# design.net
KiCad netlist of a schematic drawn in Altium Designer
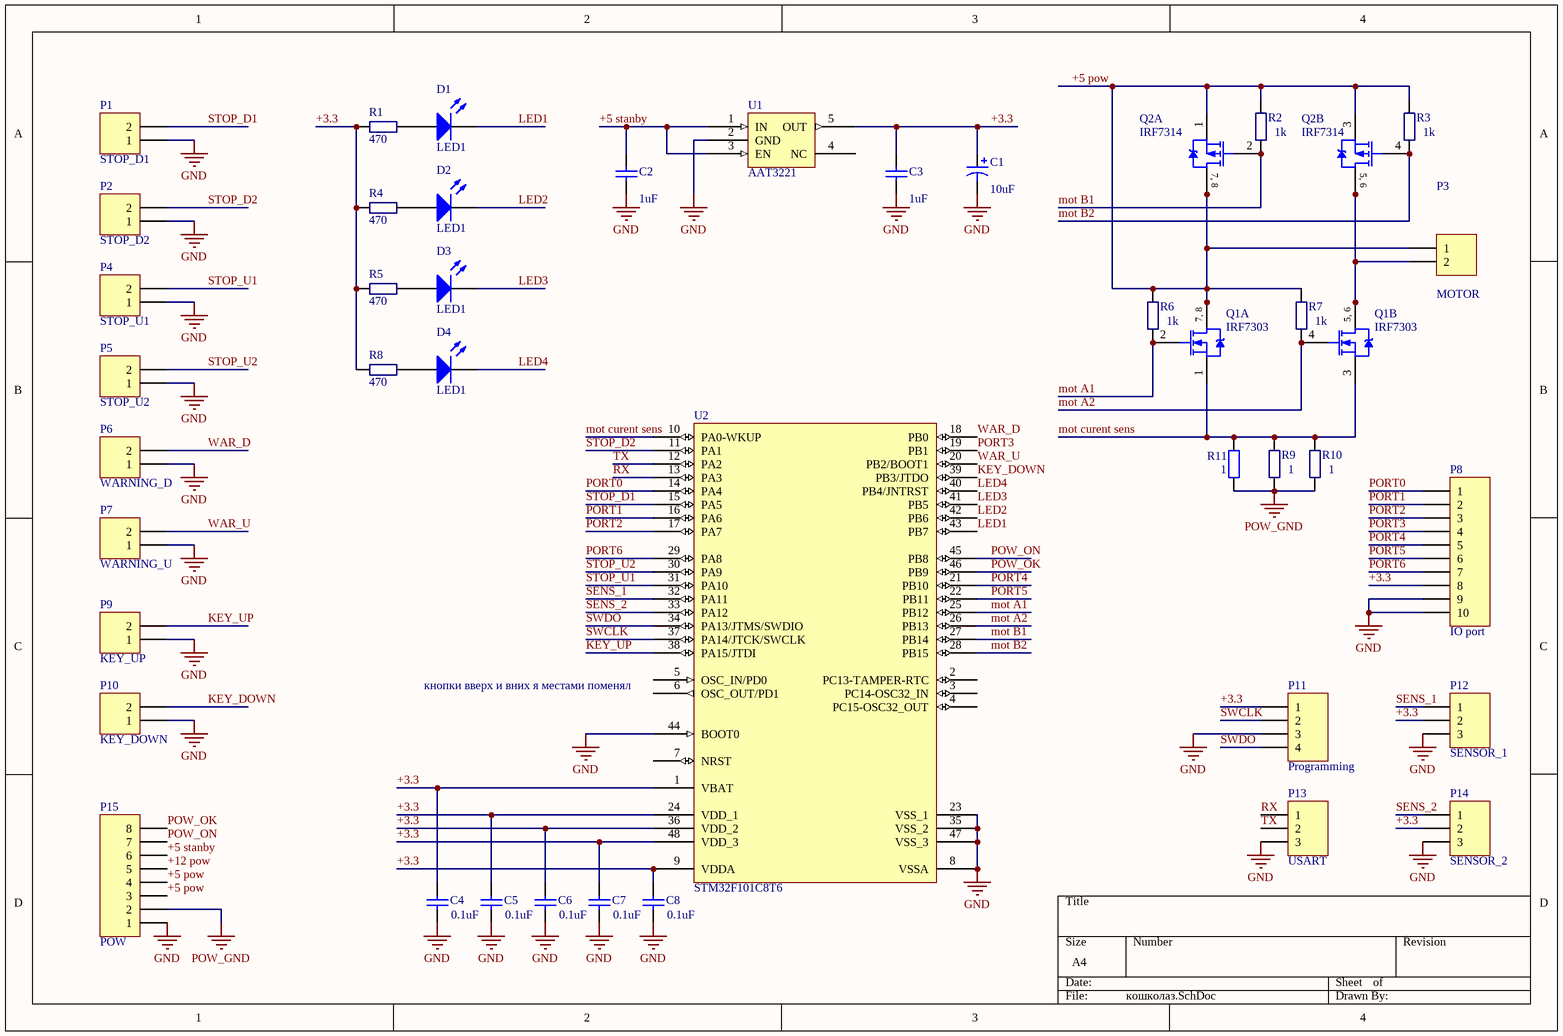
[diagram p0: кошколаз.SchDoc]

(export (version "E")
  (design (tool "Eeschema 10.0.6"))
  (components
    (comp (ref "C1")
      (value "10uF")
      (footprint "C0805")
      (description "Polarized Capacitor (Surface Mount)")
      (fields (field (name "PUBLISHER") "Altium Limited"))
      (libsource (lib "Miscellaneous Devices") (part "Cap Pol3"))
    )
    (comp (ref "C2")
      (value "1uF")
      (footprint "1608[0603]")
      (description "Capacitor (Semiconductor SIM Model)")
      (fields (field (name "PUBLISHER") "Altium Limited"))
      (libsource (lib "Miscellaneous Devices") (part "Cap Semi"))
    )
    (comp (ref "C3")
      (value "1uF")
      (footprint "1608[0603]")
      (description "Capacitor (Semiconductor SIM Model)")
      (fields (field (name "PUBLISHER") "Altium Limited"))
      (libsource (lib "Miscellaneous Devices") (part "Cap Semi"))
    )
    (comp (ref "C4")
      (value "0.1uF")
      (footprint "1608[0603]")
      (description "Capacitor (Semiconductor SIM Model)")
      (fields (field (name "PUBLISHER") "Altium Limited"))
      (libsource (lib "Miscellaneous Devices") (part "Cap Semi"))
    )
    (comp (ref "C5")
      (value "0.1uF")
      (footprint "1608[0603]")
      (description "Capacitor (Semiconductor SIM Model)")
      (fields (field (name "PUBLISHER") "Altium Limited"))
      (libsource (lib "Miscellaneous Devices") (part "Cap Semi"))
    )
    (comp (ref "C6")
      (value "0.1uF")
      (footprint "1608[0603]")
      (description "Capacitor (Semiconductor SIM Model)")
      (fields (field (name "PUBLISHER") "Altium Limited"))
      (libsource (lib "Miscellaneous Devices") (part "Cap Semi"))
    )
    (comp (ref "C7")
      (value "0.1uF")
      (footprint "1608[0603]")
      (description "Capacitor (Semiconductor SIM Model)")
      (fields (field (name "PUBLISHER") "Altium Limited"))
      (libsource (lib "Miscellaneous Devices") (part "Cap Semi"))
    )
    (comp (ref "C8")
      (value "0.1uF")
      (footprint "1608[0603]")
      (description "Capacitor (Semiconductor SIM Model)")
      (fields (field (name "PUBLISHER") "Altium Limited"))
      (libsource (lib "Miscellaneous Devices") (part "Cap Semi"))
    )
    (comp (ref "D1")
      (value "LED1")
      (footprint "LED-1")
      (description "Typical RED GaAs LED")
      (fields (field (name "PUBLISHER") "Altium Limited"))
      (libsource (lib "Miscellaneous Devices") (part "LED1"))
    )
    (comp (ref "D2")
      (value "LED1")
      (footprint "LED-1")
      (description "Typical RED GaAs LED")
      (fields (field (name "PUBLISHER") "Altium Limited"))
      (libsource (lib "Miscellaneous Devices") (part "LED1"))
    )
    (comp (ref "D3")
      (value "LED1")
      (footprint "LED-1")
      (description "Typical RED GaAs LED")
      (fields (field (name "PUBLISHER") "Altium Limited"))
      (libsource (lib "Miscellaneous Devices") (part "LED1"))
    )
    (comp (ref "D4")
      (value "LED1")
      (footprint "LED-1")
      (description "Typical RED GaAs LED")
      (fields (field (name "PUBLISHER") "Altium Limited"))
      (libsource (lib "Miscellaneous Devices") (part "LED1"))
    )
    (comp (ref "P1")
      (value "STOP_D1")
      (footprint "HDR1X2")
      (description "Header, 2-Pin")
      (fields (field (name "PUBLISHER") "Altium Limited"))
      (libsource (lib "Miscellaneous Connectors") (part "Header 2"))
    )
    (comp (ref "P2")
      (value "STOP_D2")
      (footprint "HDR1X2")
      (description "Header, 2-Pin")
      (fields (field (name "PUBLISHER") "Altium Limited"))
      (libsource (lib "Miscellaneous Connectors") (part "Header 2"))
    )
    (comp (ref "P3")
      (value "MOTOR")
      (footprint "HDR1X2")
      (description "Header, 2-Pin")
      (fields (field (name "PUBLISHER") "Altium Limited"))
      (libsource (lib "") (part "Header 2_1"))
    )
    (comp (ref "P4")
      (value "STOP_U1")
      (footprint "HDR1X2")
      (description "Header, 2-Pin")
      (fields (field (name "PUBLISHER") "Altium Limited"))
      (libsource (lib "Miscellaneous Connectors") (part "Header 2"))
    )
    (comp (ref "P5")
      (value "STOP_U2")
      (footprint "HDR1X2")
      (description "Header, 2-Pin")
      (fields (field (name "PUBLISHER") "Altium Limited"))
      (libsource (lib "Miscellaneous Connectors") (part "Header 2"))
    )
    (comp (ref "P6")
      (value "WARNING_D")
      (footprint "HDR1X2")
      (description "Header, 2-Pin")
      (fields (field (name "PUBLISHER") "Altium Limited"))
      (libsource (lib "Miscellaneous Connectors") (part "Header 2"))
    )
    (comp (ref "P7")
      (value "WARNING_U")
      (footprint "HDR1X2")
      (description "Header, 2-Pin")
      (fields (field (name "PUBLISHER") "Altium Limited"))
      (libsource (lib "Miscellaneous Connectors") (part "Header 2"))
    )
    (comp (ref "P8")
      (value "IO port")
      (footprint "HDR1X10")
      (description "Header, 10-Pin")
      (fields (field (name "PUBLISHER") "Altium Limited"))
      (libsource (lib "Miscellaneous Connectors") (part "Header 10"))
    )
    (comp (ref "P9")
      (value "KEY_UP")
      (footprint "HDR1X2")
      (description "Header, 2-Pin")
      (fields (field (name "PUBLISHER") "Altium Limited"))
      (libsource (lib "Miscellaneous Connectors") (part "Header 2"))
    )
    (comp (ref "P10")
      (value "KEY_DOWN")
      (footprint "HDR1X2")
      (description "Header, 2-Pin")
      (fields (field (name "PUBLISHER") "Altium Limited"))
      (libsource (lib "Miscellaneous Connectors") (part "Header 2"))
    )
    (comp (ref "P11")
      (value "Programming")
      (footprint "HDR1X4")
      (description "Header, 4-Pin")
      (fields (field (name "PUBLISHER") "Altium Limited"))
      (libsource (lib "Miscellaneous Connectors") (part "Header 4"))
    )
    (comp (ref "P12")
      (value "SENSOR_1")
      (footprint "HDR1X3")
      (description "Header, 3-Pin")
      (fields (field (name "PUBLISHER") "Altium Limited"))
      (libsource (lib "Miscellaneous Connectors") (part "Header 3"))
    )
    (comp (ref "P13")
      (value "USART")
      (footprint "HDR1X3")
      (description "Header, 3-Pin")
      (fields (field (name "PUBLISHER") "Altium Limited"))
      (libsource (lib "Miscellaneous Connectors") (part "Header 3"))
    )
    (comp (ref "P14")
      (value "SENSOR_2")
      (footprint "HDR1X3")
      (description "Header, 3-Pin")
      (fields (field (name "PUBLISHER") "Altium Limited"))
      (libsource (lib "Miscellaneous Connectors") (part "Header 3"))
    )
    (comp (ref "P15")
      (value "POW")
      (footprint "HDR1X8")
      (description "Header, 8-Pin")
      (fields (field (name "PUBLISHER") "Altium Limited"))
      (libsource (lib "Miscellaneous Connectors") (part "Header 8"))
    )
    (comp (ref "Q1")
      (value "IRF7303")
      (footprint "SO-8_N")
      (description "HEXFET Power MOSFET")
      (fields (field (name "PUBLISHER") "Altium Limited"))
      (libsource (lib "IR Discrete MOSFET - Power") (part "IRF7303"))
    )
    (comp (ref "Q2")
      (value "IRF7314")
      (footprint "SO-8_N")
      (description "HEXFET Power MOSFET")
      (fields (field (name "PUBLISHER") "Altium Limited"))
      (libsource (lib "IR Discrete MOSFET - Power") (part "IRF7314"))
    )
    (comp (ref "R1")
      (value "470")
      (footprint "J1-0603")
      (description "Resistor")
      (fields (field (name "PUBLISHER") "Altium Limited"))
      (libsource (lib "LockLib") (part "Res_SMD"))
    )
    (comp (ref "R2")
      (value "1k")
      (footprint "J1-0603")
      (description "Resistor")
      (fields (field (name "PUBLISHER") "Altium Limited"))
      (libsource (lib "LockLib") (part "Res_SMD"))
    )
    (comp (ref "R3")
      (value "1k")
      (footprint "J1-0603")
      (description "Resistor")
      (fields (field (name "PUBLISHER") "Altium Limited"))
      (libsource (lib "LockLib") (part "Res_SMD"))
    )
    (comp (ref "R4")
      (value "470")
      (footprint "J1-0603")
      (description "Resistor")
      (fields (field (name "PUBLISHER") "Altium Limited"))
      (libsource (lib "LockLib") (part "Res_SMD"))
    )
    (comp (ref "R5")
      (value "470")
      (footprint "J1-0603")
      (description "Resistor")
      (fields (field (name "PUBLISHER") "Altium Limited"))
      (libsource (lib "LockLib") (part "Res_SMD"))
    )
    (comp (ref "R6")
      (value "1k")
      (footprint "J1-0603")
      (description "Resistor")
      (fields (field (name "PUBLISHER") "Altium Limited"))
      (libsource (lib "LockLib") (part "Res_SMD"))
    )
    (comp (ref "R7")
      (value "1k")
      (footprint "J1-0603")
      (description "Resistor")
      (fields (field (name "PUBLISHER") "Altium Limited"))
      (libsource (lib "LockLib") (part "Res_SMD"))
    )
    (comp (ref "R8")
      (value "470")
      (footprint "J1-0603")
      (description "Resistor")
      (fields (field (name "PUBLISHER") "Altium Limited"))
      (libsource (lib "LockLib") (part "Res_SMD"))
    )
    (comp (ref "R9")
      (value "1")
      (footprint "6-0805_N")
      (description "Resistor")
      (fields (field (name "PUBLISHER") "Altium Limited"))
      (libsource (lib "LockLib") (part "Res_SMD"))
    )
    (comp (ref "R10")
      (value "1")
      (footprint "6-0805_N")
      (description "Resistor")
      (fields (field (name "PUBLISHER") "Altium Limited"))
      (libsource (lib "LockLib") (part "Res_SMD"))
    )
    (comp (ref "R11")
      (value "1")
      (footprint "AXIAL-0.4")
      (description "Resistor")
      (fields (field (name "PUBLISHER") "Altium Limited"))
      (libsource (lib "Miscellaneous Devices") (part "Res2"))
    )
    (comp (ref "U1")
      (value "AAT3221")
      (footprint "SOT23-5")
      (description "Low Dropout Linear Regulator")
      (libsource (lib "LockLib") (part "AAT3221"))
    )
    (comp (ref "U2")
      (value "STM32F101C8T6")
      (footprint "LQFP48_M")
      (description "STM32 ARM-based 32-bit MCU with 64 Kbytes Flash, 48-pin LQFP, Industrial Temperature")
      (fields (field (name "PUBLISHER") "Altium Limited"))
      (libsource (lib "ST Microcontroller 32-Bit STM32") (part "STM32F101C8T6"))
    )
  )
  (nets
    (net (code "1") (name "/+3.3") (class "Default")
      (node (ref "C1") (pin "1") (pinfunction "1_1") (pintype "passive"))
      (node (ref "C3") (pin "2") (pinfunction "2_2") (pintype "passive"))
      (node (ref "C4") (pin "2") (pinfunction "2_2") (pintype "passive"))
      (node (ref "C5") (pin "2") (pinfunction "2_2") (pintype "passive"))
      (node (ref "C6") (pin "2") (pinfunction "2_2") (pintype "passive"))
      (node (ref "C7") (pin "2") (pinfunction "2_2") (pintype "passive"))
      (node (ref "C8") (pin "2") (pinfunction "2_2") (pintype "passive"))
      (node (ref "P11") (pin "1") (pinfunction "1_1") (pintype "passive"))
      (node (ref "P12") (pin "2") (pinfunction "2_2") (pintype "passive"))
      (node (ref "P14") (pin "2") (pinfunction "2_2") (pintype "passive"))
      (node (ref "P8") (pin "8") (pinfunction "8_8") (pintype "passive"))
      (node (ref "R1") (pin "2") (pinfunction "2_2") (pintype "passive"))
      (node (ref "R4") (pin "2") (pinfunction "2_2") (pintype "passive"))
      (node (ref "R5") (pin "2") (pinfunction "2_2") (pintype "passive"))
      (node (ref "R8") (pin "2") (pinfunction "2_2") (pintype "passive"))
      (node (ref "U1") (pin "5") (pinfunction "OUT_5") (pintype "output"))
      (node (ref "U2") (pin "1") (pinfunction "VBAT_1") (pintype "power_in"))
      (node (ref "U2") (pin "24") (pinfunction "VDD_1_24") (pintype "power_in"))
      (node (ref "U2") (pin "36") (pinfunction "VDD_2_36") (pintype "power_in"))
      (node (ref "U2") (pin "48") (pinfunction "VDD_3_48") (pintype "power_in"))
      (node (ref "U2") (pin "9") (pinfunction "VDDA_9") (pintype "power_in"))
    )
    (net (code "2") (name "/+5 pow") (class "Default")
      (node (ref "P15") (pin "3") (pinfunction "3_3") (pintype "passive"))
      (node (ref "P15") (pin "4") (pinfunction "4_4") (pintype "passive"))
      (node (ref "P3") (pin "1") (pinfunction "1_1") (pintype "passive"))
      (node (ref "Q1") (pin "7") (pinfunction "D_7") (pintype "passive"))
      (node (ref "Q1") (pin "8") (pinfunction "D_8") (pintype "passive"))
      (node (ref "Q2") (pin "1") (pinfunction "S_1") (pintype "passive"))
      (node (ref "Q2") (pin "3") (pinfunction "S_3") (pintype "passive"))
      (node (ref "Q2") (pin "7") (pinfunction "D_7") (pintype "passive"))
      (node (ref "Q2") (pin "8") (pinfunction "D_8") (pintype "passive"))
      (node (ref "R2") (pin "2") (pinfunction "2_2") (pintype "passive"))
      (node (ref "R3") (pin "2") (pinfunction "2_2") (pintype "passive"))
      (node (ref "R6") (pin "2") (pinfunction "2_2") (pintype "passive"))
      (node (ref "R7") (pin "2") (pinfunction "2_2") (pintype "passive"))
    )
    (net (code "3") (name "/+5 stanby") (class "Default")
      (node (ref "C2") (pin "2") (pinfunction "2_2") (pintype "passive"))
      (node (ref "P15") (pin "6") (pinfunction "6_6") (pintype "passive"))
      (node (ref "U1") (pin "1") (pinfunction "IN_1") (pintype "input"))
      (node (ref "U1") (pin "3") (pinfunction "EN_3") (pintype "input"))
    )
    (net (code "4") (name "/+12 pow") (class "Default")
      (node (ref "P15") (pin "5") (pinfunction "5_5") (pintype "passive"))
    )
    (net (code "5") (name "/KEY_DOWN") (class "Default")
      (node (ref "P10") (pin "2") (pinfunction "2_2") (pintype "passive"))
      (node (ref "U2") (pin "39") (pinfunction "PB3/JTDO_39") (pintype "bidirectional"))
    )
    (net (code "6") (name "/KEY_UP") (class "Default")
      (node (ref "P9") (pin "2") (pinfunction "2_2") (pintype "passive"))
      (node (ref "U2") (pin "38") (pinfunction "PA15/JTDI_38") (pintype "bidirectional"))
    )
    (net (code "7") (name "/LED1") (class "Default")
      (node (ref "D1") (pin "2") (pinfunction "K_2") (pintype "passive"))
      (node (ref "U2") (pin "43") (pinfunction "PB7_43") (pintype "bidirectional"))
    )
    (net (code "8") (name "/LED2") (class "Default")
      (node (ref "D2") (pin "2") (pinfunction "K_2") (pintype "passive"))
      (node (ref "U2") (pin "42") (pinfunction "PB6_42") (pintype "bidirectional"))
    )
    (net (code "9") (name "/LED3") (class "Default")
      (node (ref "D3") (pin "2") (pinfunction "K_2") (pintype "passive"))
      (node (ref "U2") (pin "41") (pinfunction "PB5_41") (pintype "bidirectional"))
    )
    (net (code "10") (name "/LED4") (class "Default")
      (node (ref "D4") (pin "2") (pinfunction "K_2") (pintype "passive"))
      (node (ref "U2") (pin "40") (pinfunction "PB4/JNTRST_40") (pintype "bidirectional"))
    )
    (net (code "11") (name "/PORT0") (class "Default")
      (node (ref "P8") (pin "1") (pinfunction "1_1") (pintype "passive"))
      (node (ref "U2") (pin "14") (pinfunction "PA4_14") (pintype "bidirectional"))
    )
    (net (code "12") (name "/PORT1") (class "Default")
      (node (ref "P8") (pin "2") (pinfunction "2_2") (pintype "passive"))
      (node (ref "U2") (pin "16") (pinfunction "PA6_16") (pintype "bidirectional"))
    )
    (net (code "13") (name "/PORT2") (class "Default")
      (node (ref "P8") (pin "3") (pinfunction "3_3") (pintype "passive"))
      (node (ref "U2") (pin "17") (pinfunction "PA7_17") (pintype "bidirectional"))
    )
    (net (code "14") (name "/PORT3") (class "Default")
      (node (ref "P8") (pin "4") (pinfunction "4_4") (pintype "passive"))
      (node (ref "U2") (pin "19") (pinfunction "PB1_19") (pintype "bidirectional"))
    )
    (net (code "15") (name "/PORT4") (class "Default")
      (node (ref "P8") (pin "5") (pinfunction "5_5") (pintype "passive"))
      (node (ref "U2") (pin "21") (pinfunction "PB10_21") (pintype "bidirectional"))
    )
    (net (code "16") (name "/PORT5") (class "Default")
      (node (ref "P8") (pin "6") (pinfunction "6_6") (pintype "passive"))
      (node (ref "U2") (pin "22") (pinfunction "PB11_22") (pintype "bidirectional"))
    )
    (net (code "17") (name "/PORT6") (class "Default")
      (node (ref "P8") (pin "7") (pinfunction "7_7") (pintype "passive"))
      (node (ref "U2") (pin "29") (pinfunction "PA8_29") (pintype "bidirectional"))
    )
    (net (code "18") (name "/POW_OK") (class "Default")
      (node (ref "P15") (pin "8") (pinfunction "8_8") (pintype "passive"))
      (node (ref "U2") (pin "46") (pinfunction "PB9_46") (pintype "bidirectional"))
    )
    (net (code "19") (name "/POW_ON") (class "Default")
      (node (ref "P15") (pin "7") (pinfunction "7_7") (pintype "passive"))
      (node (ref "U2") (pin "45") (pinfunction "PB8_45") (pintype "bidirectional"))
    )
    (net (code "20") (name "/RX") (class "Default")
      (node (ref "P13") (pin "1") (pinfunction "1_1") (pintype "passive"))
      (node (ref "U2") (pin "13") (pinfunction "PA3_13") (pintype "bidirectional"))
    )
    (net (code "21") (name "/SENS_1") (class "Default")
      (node (ref "P12") (pin "1") (pinfunction "1_1") (pintype "passive"))
      (node (ref "U2") (pin "32") (pinfunction "PA11_32") (pintype "bidirectional"))
    )
    (net (code "22") (name "/SENS_2") (class "Default")
      (node (ref "P14") (pin "1") (pinfunction "1_1") (pintype "passive"))
      (node (ref "U2") (pin "33") (pinfunction "PA12_33") (pintype "bidirectional"))
    )
    (net (code "23") (name "/STOP_D1") (class "Default")
      (node (ref "P1") (pin "2") (pinfunction "2_2") (pintype "passive"))
      (node (ref "U2") (pin "15") (pinfunction "PA5_15") (pintype "bidirectional"))
    )
    (net (code "24") (name "/STOP_D2") (class "Default")
      (node (ref "P2") (pin "2") (pinfunction "2_2") (pintype "passive"))
      (node (ref "U2") (pin "11") (pinfunction "PA1_11") (pintype "bidirectional"))
    )
    (net (code "25") (name "/STOP_U1") (class "Default")
      (node (ref "P4") (pin "2") (pinfunction "2_2") (pintype "passive"))
      (node (ref "U2") (pin "31") (pinfunction "PA10_31") (pintype "bidirectional"))
    )
    (net (code "26") (name "/STOP_U2") (class "Default")
      (node (ref "P5") (pin "2") (pinfunction "2_2") (pintype "passive"))
      (node (ref "U2") (pin "30") (pinfunction "PA9_30") (pintype "bidirectional"))
    )
    (net (code "27") (name "/SWCLK") (class "Default")
      (node (ref "P11") (pin "2") (pinfunction "2_2") (pintype "passive"))
      (node (ref "U2") (pin "37") (pinfunction "PA14/JTCK/SWCLK_37") (pintype "bidirectional"))
    )
    (net (code "28") (name "/SWDO") (class "Default")
      (node (ref "P11") (pin "4") (pinfunction "4_4") (pintype "passive"))
      (node (ref "U2") (pin "34") (pinfunction "PA13/JTMS/SWDIO_34") (pintype "bidirectional"))
    )
    (net (code "29") (name "/TX") (class "Default")
      (node (ref "P13") (pin "2") (pinfunction "2_2") (pintype "passive"))
      (node (ref "U2") (pin "12") (pinfunction "PA2_12") (pintype "bidirectional"))
    )
    (net (code "30") (name "/WAR_D") (class "Default")
      (node (ref "P6") (pin "2") (pinfunction "2_2") (pintype "passive"))
      (node (ref "U2") (pin "18") (pinfunction "PB0_18") (pintype "bidirectional"))
    )
    (net (code "31") (name "/WAR_U") (class "Default")
      (node (ref "P7") (pin "2") (pinfunction "2_2") (pintype "passive"))
      (node (ref "U2") (pin "20") (pinfunction "PB2/BOOT1_20") (pintype "bidirectional"))
    )
    (net (code "32") (name "/mot A1") (class "Default")
      (node (ref "Q1") (pin "2") (pinfunction "G_2") (pintype "passive"))
      (node (ref "R6") (pin "1") (pinfunction "1_1") (pintype "passive"))
      (node (ref "U2") (pin "25") (pinfunction "PB12_25") (pintype "bidirectional"))
    )
    (net (code "33") (name "/mot A2") (class "Default")
      (node (ref "Q1") (pin "4") (pinfunction "G_4") (pintype "passive"))
      (node (ref "R7") (pin "1") (pinfunction "1_1") (pintype "passive"))
      (node (ref "U2") (pin "26") (pinfunction "PB13_26") (pintype "bidirectional"))
    )
    (net (code "34") (name "/mot B1") (class "Default")
      (node (ref "Q2") (pin "2") (pinfunction "G_2") (pintype "passive"))
      (node (ref "R2") (pin "1") (pinfunction "1_1") (pintype "passive"))
      (node (ref "U2") (pin "27") (pinfunction "PB14_27") (pintype "bidirectional"))
    )
    (net (code "35") (name "/mot B2") (class "Default")
      (node (ref "Q2") (pin "4") (pinfunction "G_4") (pintype "passive"))
      (node (ref "R3") (pin "1") (pinfunction "1_1") (pintype "passive"))
      (node (ref "U2") (pin "28") (pinfunction "PB15_28") (pintype "bidirectional"))
    )
    (net (code "36") (name "/mot curent sens") (class "Default")
      (node (ref "Q1") (pin "1") (pinfunction "S_1") (pintype "passive"))
      (node (ref "Q1") (pin "3") (pinfunction "S_3") (pintype "passive"))
      (node (ref "R10") (pin "2") (pinfunction "2_2") (pintype "passive"))
      (node (ref "R11") (pin "2") (pinfunction "2_2") (pintype "passive"))
      (node (ref "R9") (pin "2") (pinfunction "2_2") (pintype "passive"))
      (node (ref "U2") (pin "10") (pinfunction "PA0-WKUP_10") (pintype "bidirectional"))
    )
    (net (code "37") (name "GND") (class "Default")
      (node (ref "C1") (pin "2") (pinfunction "2_2") (pintype "passive"))
      (node (ref "C2") (pin "1") (pinfunction "1_1") (pintype "passive"))
      (node (ref "C3") (pin "1") (pinfunction "1_1") (pintype "passive"))
      (node (ref "C4") (pin "1") (pinfunction "1_1") (pintype "passive"))
      (node (ref "C5") (pin "1") (pinfunction "1_1") (pintype "passive"))
      (node (ref "C6") (pin "1") (pinfunction "1_1") (pintype "passive"))
      (node (ref "C7") (pin "1") (pinfunction "1_1") (pintype "passive"))
      (node (ref "C8") (pin "1") (pinfunction "1_1") (pintype "passive"))
      (node (ref "P1") (pin "1") (pinfunction "1_1") (pintype "passive"))
      (node (ref "P10") (pin "1") (pinfunction "1_1") (pintype "passive"))
      (node (ref "P11") (pin "3") (pinfunction "3_3") (pintype "passive"))
      (node (ref "P12") (pin "3") (pinfunction "3_3") (pintype "passive"))
      (node (ref "P13") (pin "3") (pinfunction "3_3") (pintype "passive"))
      (node (ref "P14") (pin "3") (pinfunction "3_3") (pintype "passive"))
      (node (ref "P15") (pin "1") (pinfunction "1_1") (pintype "passive"))
      (node (ref "P2") (pin "1") (pinfunction "1_1") (pintype "passive"))
      (node (ref "P4") (pin "1") (pinfunction "1_1") (pintype "passive"))
      (node (ref "P5") (pin "1") (pinfunction "1_1") (pintype "passive"))
      (node (ref "P6") (pin "1") (pinfunction "1_1") (pintype "passive"))
      (node (ref "P7") (pin "1") (pinfunction "1_1") (pintype "passive"))
      (node (ref "P8") (pin "10") (pinfunction "10_10") (pintype "passive"))
      (node (ref "P8") (pin "9") (pinfunction "9_9") (pintype "passive"))
      (node (ref "P9") (pin "1") (pinfunction "1_1") (pintype "passive"))
      (node (ref "U1") (pin "2") (pinfunction "GND_2") (pintype "power_in"))
      (node (ref "U2") (pin "23") (pinfunction "VSS_1_23") (pintype "power_in"))
      (node (ref "U2") (pin "35") (pinfunction "VSS_2_35") (pintype "power_in"))
      (node (ref "U2") (pin "44") (pinfunction "BOOT0_44") (pintype "input"))
      (node (ref "U2") (pin "47") (pinfunction "VSS_3_47") (pintype "power_in"))
      (node (ref "U2") (pin "8") (pinfunction "VSSA_8") (pintype "power_in"))
    )
    (net (code "38") (name "Net-(D1-A)") (class "Default")
      (node (ref "D1") (pin "1") (pinfunction "A_1") (pintype "passive"))
      (node (ref "R1") (pin "1") (pinfunction "1_1") (pintype "passive"))
    )
    (net (code "39") (name "Net-(D2-A)") (class "Default")
      (node (ref "D2") (pin "1") (pinfunction "A_1") (pintype "passive"))
      (node (ref "R4") (pin "1") (pinfunction "1_1") (pintype "passive"))
    )
    (net (code "40") (name "Net-(D3-A)") (class "Default")
      (node (ref "D3") (pin "1") (pinfunction "A_1") (pintype "passive"))
      (node (ref "R5") (pin "1") (pinfunction "1_1") (pintype "passive"))
    )
    (net (code "41") (name "Net-(D4-A)") (class "Default")
      (node (ref "D4") (pin "1") (pinfunction "A_1") (pintype "passive"))
      (node (ref "R8") (pin "1") (pinfunction "1_1") (pintype "passive"))
    )
    (net (code "42") (name "Net-(P3-Pad2)") (class "Default")
      (node (ref "P3") (pin "2") (pinfunction "2_2") (pintype "passive"))
      (node (ref "Q1") (pin "5") (pinfunction "D_5") (pintype "passive"))
      (node (ref "Q1") (pin "6") (pinfunction "D_6") (pintype "passive"))
      (node (ref "Q2") (pin "5") (pinfunction "D_5") (pintype "passive"))
      (node (ref "Q2") (pin "6") (pinfunction "D_6") (pintype "passive"))
    )
    (net (code "43") (name "POW_GND") (class "Default")
      (node (ref "P15") (pin "2") (pinfunction "2_2") (pintype "passive"))
      (node (ref "R10") (pin "1") (pinfunction "1_1") (pintype "passive"))
      (node (ref "R11") (pin "1") (pinfunction "1_1") (pintype "passive"))
      (node (ref "R9") (pin "1") (pinfunction "1_1") (pintype "passive"))
    )
    (net (code "44") (name "unconnected-(U1-NC-Pad4)") (class "Default")
      (node (ref "U1") (pin "4") (pinfunction "NC_4") (pintype "passive"))
    )
    (net (code "45") (name "unconnected-(U2-NRST-Pad7)") (class "Default")
      (node (ref "U2") (pin "7") (pinfunction "NRST_7") (pintype "bidirectional"))
    )
    (net (code "46") (name "unconnected-(U2-OSC_IN{slash}PD0-Pad5)") (class "Default")
      (node (ref "U2") (pin "5") (pinfunction "OSC_IN/PD0_5") (pintype "input"))
    )
    (net (code "47") (name "unconnected-(U2-OSC_OUT{slash}PD1-Pad6)") (class "Default")
      (node (ref "U2") (pin "6") (pinfunction "OSC_OUT/PD1_6") (pintype "output"))
    )
    (net (code "48") (name "unconnected-(U2-PC13-TAMPER-RTC-Pad2)") (class "Default")
      (node (ref "U2") (pin "2") (pinfunction "PC13-TAMPER-RTC_2") (pintype "bidirectional"))
    )
    (net (code "49") (name "unconnected-(U2-PC14-OSC32_IN-Pad3)") (class "Default")
      (node (ref "U2") (pin "3") (pinfunction "PC14-OSC32_IN_3") (pintype "bidirectional"))
    )
    (net (code "50") (name "unconnected-(U2-PC15-OSC32_OUT-Pad4)") (class "Default")
      (node (ref "U2") (pin "4") (pinfunction "PC15-OSC32_OUT_4") (pintype "bidirectional"))
    )
  )
)
